# sensor.net
KiCad netlist of a schematic drawn in EAGLE
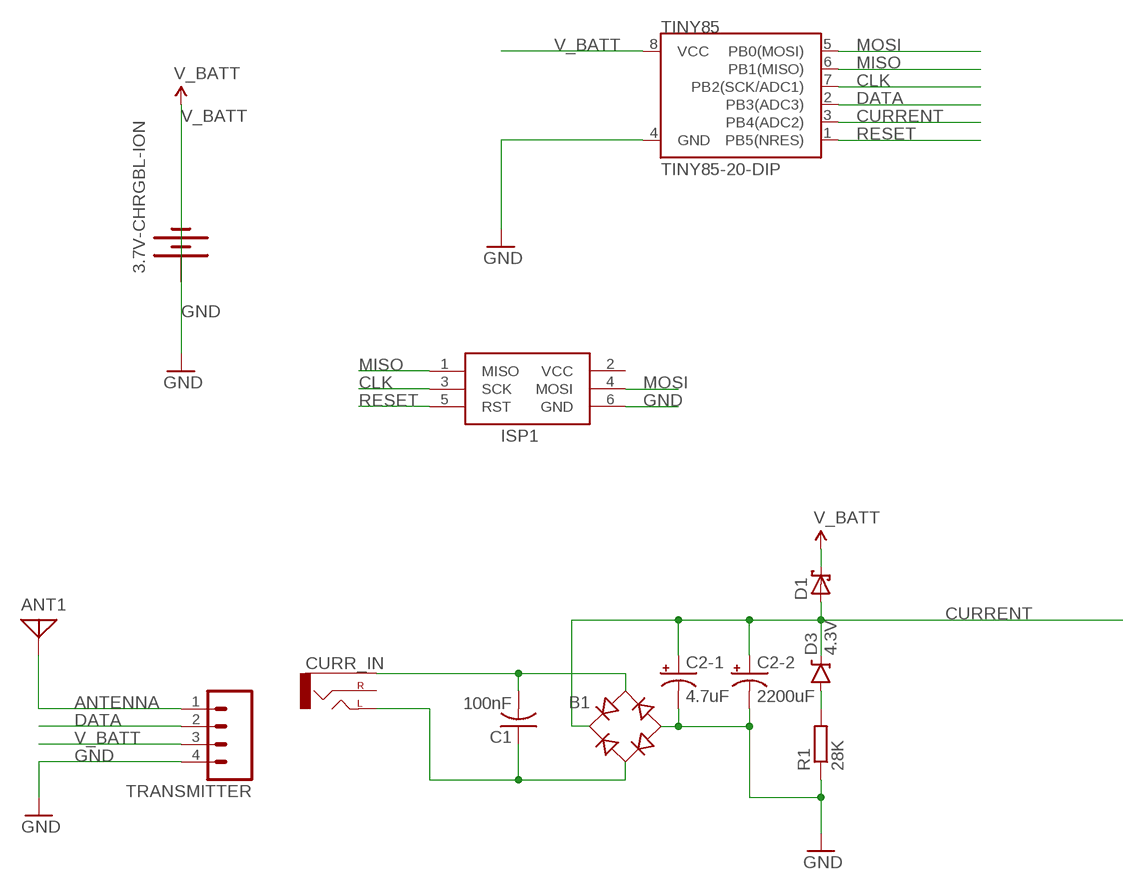
[diagram p0: schematic, sheet 1]

(export (version "E")
  (design (tool "Eeschema 10.0.6"))
  (components
    (comp (ref "3.7V-CHRGBL-ION")
      (value "BATTERY20PTH")
      (footprint "eagle-import:BATTCOM_20MM_PTH")
      (libsource (lib "eagle-import") (part "BATTERY20PTH"))
    )
    (comp (ref "ANT1")
      (value "ANTENNA")
      (footprint "eagle-import:PAD-01")
      (libsource (lib "eagle-import") (part "ANTENNA"))
    )
    (comp (ref "B1")
      (value "B-DIL")
      (footprint "eagle-import:B-DIL")
      (libsource (lib "eagle-import") (part "B-DIL"))
    )
    (comp (ref "C1")
      (value "100nF")
      (footprint "eagle-import:C075-032X103")
      (libsource (lib "eagle-import") (part "C-US075-032X103"))
    )
    (comp (ref "C2-1")
      (value "4.7uF")
      (footprint "eagle-import:E5-4")
      (libsource (lib "eagle-import") (part "CPOL-USE5-4"))
    )
    (comp (ref "C2-2")
      (value "2200uF")
      (footprint "eagle-import:CPOL-RADIAL-1000UF-25V")
      (libsource (lib "eagle-import") (part "CAP_POLPTH4"))
    )
    (comp (ref "CURR_IN")
      (value "AUDIO-JACKPTH")
      (footprint "eagle-import:AUDIO-JACK")
      (libsource (lib "eagle-import") (part "AUDIO-JACKPTH"))
    )
    (comp (ref "D1")
      (value "SCHOTTKY-DIODEDO35-7")
      (footprint "eagle-import:DO35-7")
      (libsource (lib "eagle-import") (part "SCHOTTKY-DIODEDO35-7"))
    )
    (comp (ref "D3")
      (value "4.3V")
      (footprint "eagle-import:DIODE-ZENER")
      (libsource (lib "eagle-import") (part "DIODE-ZENERPTH"))
    )
    (comp (ref "ISP1")
      (value "AVRISP-BOX")
      (footprint "eagle-import:AVRISP-BOX")
      (libsource (lib "eagle-import") (part "AVRISP-BOX"))
    )
    (comp (ref "R1")
      (value "28K")
      (footprint "eagle-import:0207_10")
      (libsource (lib "eagle-import") (part "R-EU_0207/10"))
    )
    (comp (ref "TINY85")
      (value "TINY85-20-DIP")
      (footprint "eagle-import:DIP08")
      (libsource (lib "eagle-import") (part "ATTINY45TINY85-20-DIP"))
    )
    (comp (ref "TRANSMITTER")
      (value "M04PTH")
      (footprint "eagle-import:1X04")
      (libsource (lib "eagle-import") (part "M04PTH"))
    )
  )
  (nets
    (net (code "1") (name "/ANTENNA") (class "Default")
      (node (ref "ANT1") (pin "1") (pinfunction "1_1") (pintype "output"))
      (node (ref "TRANSMITTER") (pin "1") (pinfunction "1_1") (pintype "passive"))
    )
    (net (code "2") (name "/CLK") (class "Default")
      (node (ref "ISP1") (pin "3") (pinfunction "SCK_3") (pintype "output"))
      (node (ref "TINY85") (pin "7") (pinfunction "PB2(SCK/ADC1)_7") (pintype "bidirectional"))
    )
    (net (code "3") (name "/CURRENT") (class "Default")
      (node (ref "B1") (pin "+") (pinfunction "+_+") (pintype "passive"))
      (node (ref "C2-1") (pin "+") (pinfunction "+_+") (pintype "passive"))
      (node (ref "C2-2") (pin "+") (pinfunction "+_+") (pintype "passive"))
      (node (ref "D1") (pin "A") (pinfunction "A_A") (pintype "passive"))
      (node (ref "D3") (pin "P$1") (pinfunction "C_P$1") (pintype "passive"))
      (node (ref "TINY85") (pin "3") (pinfunction "PB4(ADC2)_3") (pintype "bidirectional"))
    )
    (net (code "4") (name "/DATA") (class "Default")
      (node (ref "TINY85") (pin "2") (pinfunction "PB3(ADC3)_2") (pintype "bidirectional"))
      (node (ref "TRANSMITTER") (pin "2") (pinfunction "2_2") (pintype "passive"))
    )
    (net (code "5") (name "/MISO") (class "Default")
      (node (ref "ISP1") (pin "1") (pinfunction "MISO_1") (pintype "input"))
      (node (ref "TINY85") (pin "6") (pinfunction "PB1(MISO)_6") (pintype "bidirectional"))
    )
    (net (code "6") (name "/MOSI") (class "Default")
      (node (ref "ISP1") (pin "4") (pinfunction "MOSI_4") (pintype "output"))
      (node (ref "TINY85") (pin "5") (pinfunction "PB0(MOSI)_5") (pintype "bidirectional"))
    )
    (net (code "7") (name "/RESET") (class "Default")
      (node (ref "ISP1") (pin "5") (pinfunction "RST_5") (pintype "output"))
      (node (ref "TINY85") (pin "1") (pinfunction "PB5(NRES)_1") (pintype "bidirectional"))
    )
    (net (code "8") (name "/VCC") (class "Default")
      (node (ref "ISP1") (pin "2") (pinfunction "VCC_2") (pintype "power_in"))
    )
    (net (code "9") (name "GND") (class "Default")
      (node (ref "3.7V-CHRGBL-ION") (pin "2") (pinfunction "-_2") (pintype "power_in"))
      (node (ref "B1") (pin "-") (pinfunction "-_-") (pintype "passive"))
      (node (ref "C2-1") (pin "-") (pinfunction "-_-") (pintype "passive"))
      (node (ref "C2-2") (pin "-") (pinfunction "-_-") (pintype "passive"))
      (node (ref "ISP1") (pin "6") (pinfunction "GND_6") (pintype "power_in"))
      (node (ref "R1") (pin "1") (pinfunction "1_1") (pintype "passive"))
      (node (ref "TINY85") (pin "4") (pinfunction "GND_4") (pintype "bidirectional"))
      (node (ref "TRANSMITTER") (pin "4") (pinfunction "4_4") (pintype "passive"))
    )
    (net (code "10") (name "Net-(B1-PadAC1)") (class "Default")
      (node (ref "B1") (pin "AC1") (pinfunction "AC1_AC1") (pintype "passive"))
      (node (ref "C1") (pin "2") (pinfunction "2_2") (pintype "passive"))
      (node (ref "CURR_IN") (pin "SLEEVE") (pinfunction "SLEEVE_SLEEVE") (pintype "bidirectional"))
    )
    (net (code "11") (name "Net-(CURR_IN-LEFT)") (class "Default")
      (node (ref "B1") (pin "AC2") (pinfunction "AC2_AC2") (pintype "passive"))
      (node (ref "C1") (pin "1") (pinfunction "1_1") (pintype "passive"))
      (node (ref "CURR_IN") (pin "TIP") (pinfunction "LEFT_TIP") (pintype "bidirectional"))
    )
    (net (code "12") (name "Net-(D3-A)") (class "Default")
      (node (ref "D3") (pin "P$2") (pinfunction "A_P$2") (pintype "passive"))
      (node (ref "R1") (pin "2") (pinfunction "2_2") (pintype "passive"))
    )
    (net (code "13") (name "V_BATT") (class "Default")
      (node (ref "3.7V-CHRGBL-ION") (pin "1") (pinfunction "+_1") (pintype "power_in"))
      (node (ref "D1") (pin "C") (pinfunction "C_C") (pintype "passive"))
      (node (ref "TINY85") (pin "8") (pinfunction "VCC_8") (pintype "bidirectional"))
      (node (ref "TRANSMITTER") (pin "3") (pinfunction "3_3") (pintype "passive"))
    )
    (net (code "14") (name "unconnected-(CURR_IN-RIGHT-PadRING)") (class "Default")
      (node (ref "CURR_IN") (pin "RING") (pinfunction "RIGHT_RING") (pintype "bidirectional"))
    )
  )
)
